# Transformer.net
KiCad netlist of a schematic drawn in Altium Designer
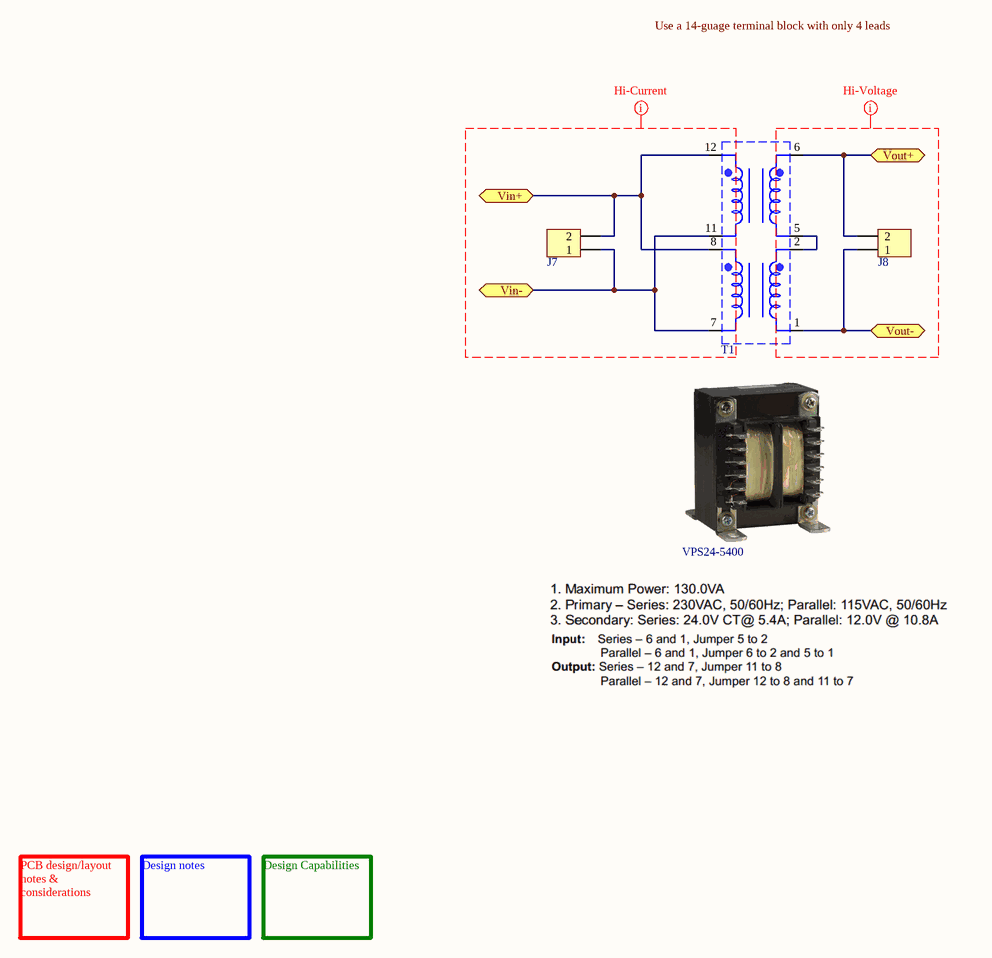
[diagram p0: Transformer.SchDoc]

(export (version "E")
  (design (tool "Eeschema 10.0.6"))
  (components
    (comp (ref "J7")
      (value "Terminal Block - 2-Position HiV/HiA")
      (footprint "TE 796739-2")
      (fields
        (field (name "MANUFACTURER") "TE Connectivity AMP Connectors")
        (field (name "MANUFACTURER PART NUMBER") "796739-2")
        (field (name "VOLTAGE") "600V")
      )
      (libsource (lib "Local Library") (part "Terminal Block - 2-Position HiV/HiA"))
    )
    (comp (ref "J8")
      (value "Terminal Block - 2-Position HiV/HiA")
      (footprint "TE 796739-2")
      (fields
        (field (name "MANUFACTURER") "TE Connectivity AMP Connectors")
        (field (name "MANUFACTURER PART NUMBER") "796739-2")
        (field (name "VOLTAGE") "600V")
      )
      (libsource (lib "") (part "Terminal Block - 2-Position HiV/HiA_1"))
    )
    (comp (ref "T1")
      (value "Transformer Connector")
      (libsource (lib "Local Library") (part "Transformer Connector"))
    )
    (comp (ref "Transformer1")
      (value "Transformer")
      (footprint "Transformer")
      (fields
        (field (name "MANUFACTURER") "Triad Magnetics")
        (field (name "MANUFACTURER PART NUMBER") "VPS24-5400")
      )
      (libsource (lib "Local Library") (part "Transformer"))
    )
  )
  (nets
    (net (code "2") (name "/Vin+") (class "Default")
      (node (ref "J7") (pin "2") (pinfunction "2_2") (pintype "passive"))
      (node (ref "T1") (pin "12") (pinfunction "12_12") (pintype "passive"))
      (node (ref "T1") (pin "8") (pinfunction "8_8") (pintype "passive"))
    )
    (net (code "3") (name "/Vin-") (class "Default")
      (node (ref "J7") (pin "1") (pinfunction "1_1") (pintype "passive"))
      (node (ref "T1") (pin "11") (pinfunction "11_11") (pintype "passive"))
      (node (ref "T1") (pin "7") (pinfunction "7_7") (pintype "passive"))
    )
    (net (code "4") (name "/Vout+") (class "Default")
      (node (ref "J8") (pin "2") (pinfunction "2_2") (pintype "passive"))
      (node (ref "T1") (pin "6") (pinfunction "6_6") (pintype "passive"))
    )
    (net (code "5") (name "/Vout-") (class "Default")
      (node (ref "J8") (pin "1") (pinfunction "1_1") (pintype "passive"))
      (node (ref "T1") (pin "1") (pinfunction "1_1") (pintype "passive"))
    )
    (net (code "6") (name "Net-(T1-Pad2)") (class "Default")
      (node (ref "T1") (pin "2") (pinfunction "2_2") (pintype "passive"))
      (node (ref "T1") (pin "5") (pinfunction "5_5") (pintype "passive"))
    )
  )
)
